# PowerSupply.net
KiCad netlist of a schematic drawn in Altium Designer
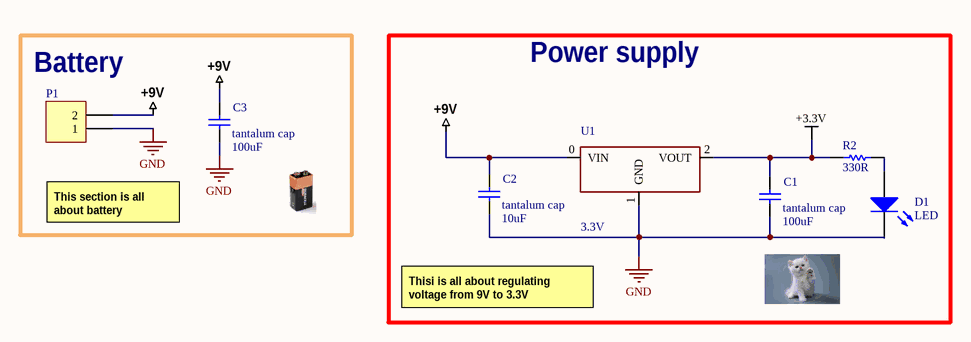
[diagram p0: PowerSupply.SchDoc]

(export (version "E")
  (design (tool "Eeschema 10.0.6"))
  (components
    (comp (ref "C1")
      (value "tantalum cap")
      (footprint "C1206tancap")
      (description "Capacitor (Semiconductor SIM Model)")
      (fields (field (name "ALTIUM_VALUE") "100uF") (field (name "PUBLISHER") "Altium Limited"))
      (libsource (lib "smartmcu") (part "Cap Semi_6"))
    )
    (comp (ref "C2")
      (value "tantalum cap")
      (footprint "C1206tancap")
      (description "Capacitor (Semiconductor SIM Model)")
      (fields (field (name "ALTIUM_VALUE") "10uF") (field (name "PUBLISHER") "Altium Limited"))
      (libsource (lib "smartmcu") (part "Cap Semi_5"))
    )
    (comp (ref "C3")
      (value "tantalum cap")
      (footprint "C1206tancap")
      (description "Capacitor (Semiconductor SIM Model)")
      (fields (field (name "ALTIUM_VALUE") "100uF") (field (name "PUBLISHER") "Altium Limited"))
      (libsource (lib "smartmcu") (part "Cap Semi_6"))
    )
    (comp (ref "D1")
      (value "LED")
      (footprint "MY_LED_0805")
      (description "Typical INFRARED GaAs LED")
      (fields (field (name "ASID PART NUMBER") "LED-AS"))
      (libsource (lib "Mylib+Rev+4") (part "LED"))
    )
    (comp (ref "P1")
      (value "~")
      (footprint "HDR1X2H3dbody")
      (description "Battery connection")
      (fields (field (name "VOLTAGE") "5V") (field (name "PUBLISHER") "Altium Limited"))
      (libsource (lib "smartmcu") (part "Header 2H"))
    )
    (comp (ref "R2")
      (value "330R")
      (footprint "MY_0805")
      (description "Standard resistor")
      (fields (field (name "ASID PART NUMBER") "Res-AS"))
      (libsource (lib "Mylib+Rev+4") (part "Res"))
    )
    (comp (ref "U1")
      (value "~")
      (footprint "4 PIN-SOT")
      (fields (field (name "VOLTAGE") "3.3V"))
      (libsource (lib "smartmcu") (part "lm1117"))
    )
  )
  (nets
    (net (code "1") (name "+3.3V") (class "Default")
      (node (ref "C1") (pin "2") (pinfunction "2_2") (pintype "passive"))
      (node (ref "R2") (pin "1") (pinfunction "1_1") (pintype "passive"))
      (node (ref "U1") (pin "2") (pinfunction "VOUT_2") (pintype "passive"))
    )
    (net (code "2") (name "+9V") (class "Default")
      (node (ref "C2") (pin "2") (pinfunction "2_2") (pintype "passive"))
      (node (ref "C3") (pin "2") (pinfunction "2_2") (pintype "passive"))
      (node (ref "P1") (pin "2") (pinfunction "2_2") (pintype "passive"))
      (node (ref "U1") (pin "0") (pinfunction "VIN_0") (pintype "passive"))
    )
    (net (code "3") (name "GND") (class "Default")
      (node (ref "C1") (pin "1") (pinfunction "1_1") (pintype "passive"))
      (node (ref "C2") (pin "1") (pinfunction "1_1") (pintype "passive"))
      (node (ref "C3") (pin "1") (pinfunction "1_1") (pintype "passive"))
      (node (ref "D1") (pin "K") (pinfunction "K_K") (pintype "passive"))
      (node (ref "P1") (pin "1") (pinfunction "1_1") (pintype "passive"))
      (node (ref "U1") (pin "1") (pinfunction "GND_1") (pintype "passive"))
    )
    (net (code "4") (name "Net-(D1-PadA)") (class "Default")
      (node (ref "D1") (pin "A") (pinfunction "A_A") (pintype "passive"))
      (node (ref "R2") (pin "2") (pinfunction "2_2") (pintype "passive"))
    )
  )
)
